# Simon-2023.net
KiCad netlist of a schematic drawn in EAGLE
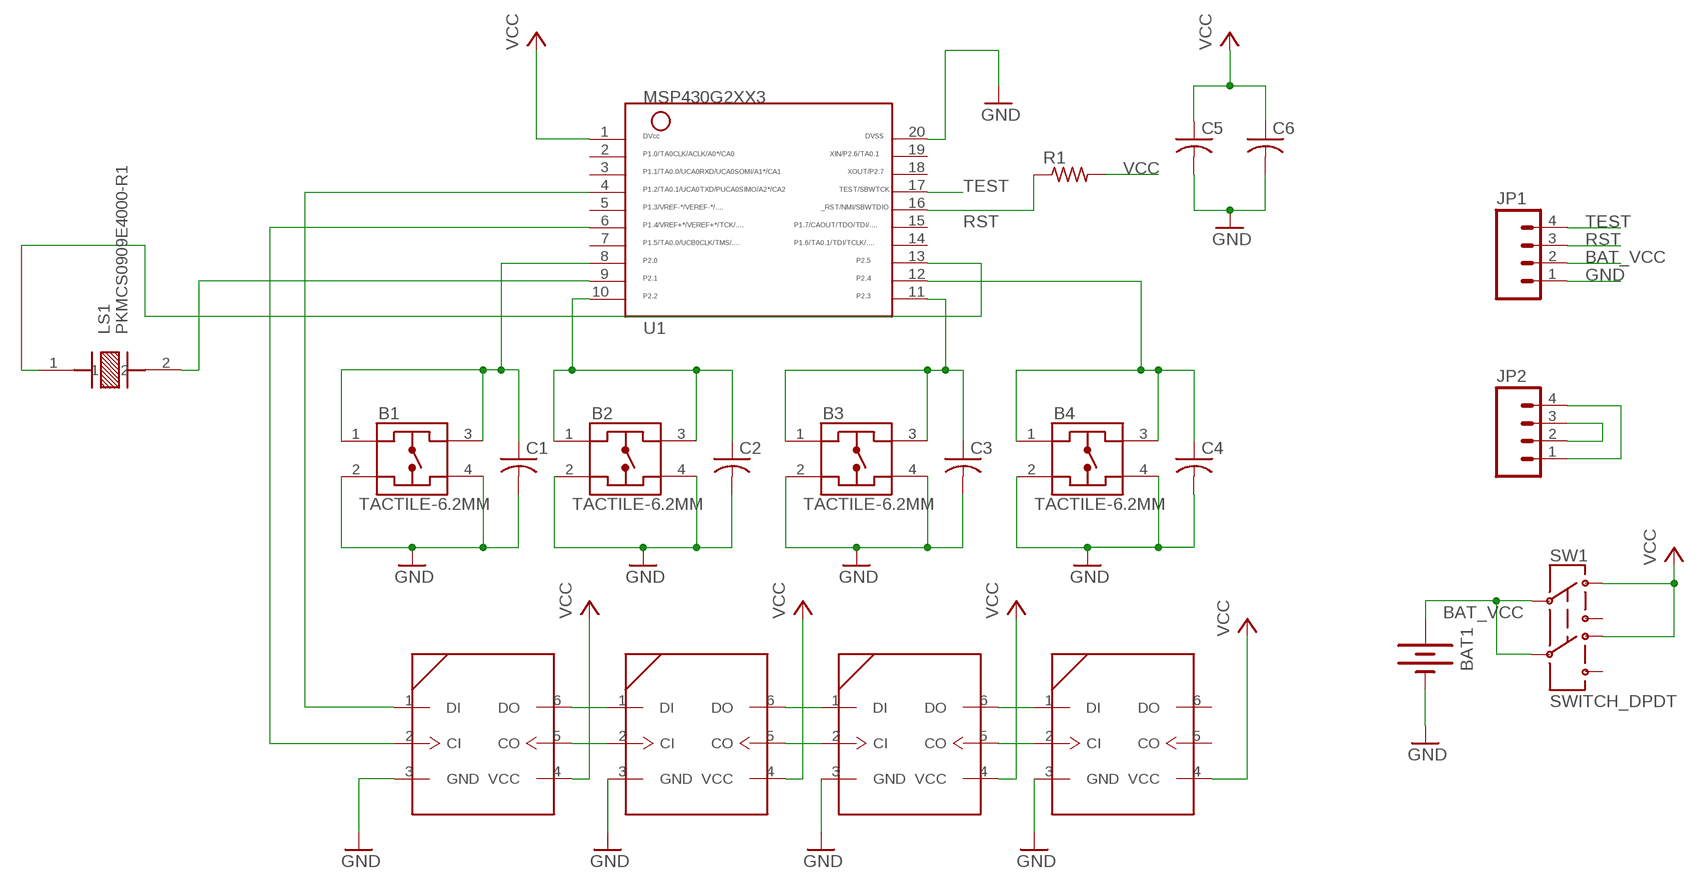
[diagram p0: schematic, sheet 1]

(export (version "E")
  (design (tool "Eeschema 10.0.6"))
  (components
    (comp (ref "B1")
      (value "TACTILE-6.2MM")
      (footprint "eagle-import:222_AM")
      (libsource (lib "eagle-import") (part "TACTILE-6.2MM"))
    )
    (comp (ref "B2")
      (value "TACTILE-6.2MM")
      (footprint "eagle-import:222_AM")
      (libsource (lib "eagle-import") (part "TACTILE-6.2MM"))
    )
    (comp (ref "B3")
      (value "TACTILE-6.2MM")
      (footprint "eagle-import:222_AM")
      (libsource (lib "eagle-import") (part "TACTILE-6.2MM"))
    )
    (comp (ref "B4")
      (value "TACTILE-6.2MM")
      (footprint "eagle-import:222_AM")
      (libsource (lib "eagle-import") (part "TACTILE-6.2MM"))
    )
    (comp (ref "BAT1")
      (value "BATTERY")
      (footprint "eagle-import:BATTERY_PACK_2AA")
      (libsource (lib "eagle-import") (part "BATTERY"))
    )
    (comp (ref "C1")
      (value "C-USC0603")
      (footprint "eagle-import:C0603")
      (libsource (lib "eagle-import") (part "C-USC0603"))
    )
    (comp (ref "C2")
      (value "C-USC0603")
      (footprint "eagle-import:C0603")
      (libsource (lib "eagle-import") (part "C-USC0603"))
    )
    (comp (ref "C3")
      (value "C-USC0603")
      (footprint "eagle-import:C0603")
      (libsource (lib "eagle-import") (part "C-USC0603"))
    )
    (comp (ref "C4")
      (value "C-USC0603")
      (footprint "eagle-import:C0603")
      (libsource (lib "eagle-import") (part "C-USC0603"))
    )
    (comp (ref "C5")
      (value "C-USC1206")
      (footprint "eagle-import:C1206")
      (libsource (lib "eagle-import") (part "C-USC1206"))
    )
    (comp (ref "C6")
      (value "C-USC0603")
      (footprint "eagle-import:C0603")
      (libsource (lib "eagle-import") (part "C-USC0603"))
    )
    (comp (ref "JP1")
      (value "M04LOCK")
      (footprint "eagle-import:1X04_LOCK")
      (libsource (lib "eagle-import") (part "M04LOCK"))
    )
    (comp (ref "JP2")
      (value "M04LOCK")
      (footprint "eagle-import:1X04_LOCK")
      (libsource (lib "eagle-import") (part "M04LOCK"))
    )
    (comp (ref "LED1")
      (value "APA102")
      (footprint "eagle-import:5050")
      (libsource (lib "eagle-import") (part "APA102"))
    )
    (comp (ref "LED2")
      (value "APA102")
      (footprint "eagle-import:5050")
      (libsource (lib "eagle-import") (part "APA102"))
    )
    (comp (ref "LED3")
      (value "APA102")
      (footprint "eagle-import:5050")
      (libsource (lib "eagle-import") (part "APA102"))
    )
    (comp (ref "LED4")
      (value "APA102")
      (footprint "eagle-import:5050")
      (libsource (lib "eagle-import") (part "APA102"))
    )
    (comp (ref "LS1")
      (value "PKMCS0909E4000-R1")
      (footprint "eagle-import:XDCR_PKMCS0909E4000-R1")
      (fields (field (name "DIGI-KEY_PART_NUMBER") "490-9647-1-ND") (field (name "MF") "Murata"))
      (libsource (lib "eagle-import") (part "PKMCS0909E4000-R1"))
    )
    (comp (ref "R1")
      (value "R-US_R1206")
      (footprint "eagle-import:R1206")
      (libsource (lib "eagle-import") (part "R-US_R1206"))
    )
    (comp (ref "SW1")
      (value "SWITCH_DPDT")
      (footprint "eagle-import:JS_DPDT_TH")
      (libsource (lib "eagle-import") (part "SWITCH_DPDT"))
    )
    (comp (ref "U1")
      (value "MSP430G2XX3TSSOP")
      (footprint "eagle-import:PW20")
      (libsource (lib "eagle-import") (part "MSP430G2XX3TSSOP"))
    )
  )
  (nets
    (net (code "1") (name "/BAT_VCC") (class "Default")
      (node (ref "BAT1") (pin "3V") (pinfunction "+_3V") (pintype "power_in"))
      (node (ref "JP1") (pin "2") (pinfunction "2_2") (pintype "passive"))
      (node (ref "SW1") (pin "2") (pinfunction "2_2") (pintype "bidirectional"))
      (node (ref "SW1") (pin "5") (pinfunction "5_5") (pintype "bidirectional"))
    )
    (net (code "2") (name "/RST") (class "Default")
      (node (ref "JP1") (pin "3") (pinfunction "3_3") (pintype "passive"))
      (node (ref "R1") (pin "1") (pinfunction "1_1") (pintype "passive"))
      (node (ref "U1") (pin "16") (pinfunction "16_16") (pintype "bidirectional"))
    )
    (net (code "3") (name "/TEST") (class "Default")
      (node (ref "JP1") (pin "4") (pinfunction "4_4") (pintype "passive"))
      (node (ref "U1") (pin "17") (pinfunction "17_17") (pintype "bidirectional"))
    )
    (net (code "4") (name "GND") (class "Default")
      (node (ref "B1") (pin "2") (pinfunction "2_2") (pintype "passive"))
      (node (ref "B1") (pin "4") (pinfunction "4_4") (pintype "passive"))
      (node (ref "B2") (pin "2") (pinfunction "2_2") (pintype "passive"))
      (node (ref "B2") (pin "4") (pinfunction "4_4") (pintype "passive"))
      (node (ref "B3") (pin "2") (pinfunction "2_2") (pintype "passive"))
      (node (ref "B3") (pin "4") (pinfunction "4_4") (pintype "passive"))
      (node (ref "B4") (pin "2") (pinfunction "2_2") (pintype "passive"))
      (node (ref "B4") (pin "4") (pinfunction "4_4") (pintype "passive"))
      (node (ref "BAT1") (pin "GND") (pinfunction "-_GND") (pintype "power_in"))
      (node (ref "C1") (pin "2") (pinfunction "2_2") (pintype "passive"))
      (node (ref "C2") (pin "2") (pinfunction "2_2") (pintype "passive"))
      (node (ref "C3") (pin "2") (pinfunction "2_2") (pintype "passive"))
      (node (ref "C4") (pin "2") (pinfunction "2_2") (pintype "passive"))
      (node (ref "C5") (pin "2") (pinfunction "2_2") (pintype "passive"))
      (node (ref "C6") (pin "2") (pinfunction "2_2") (pintype "passive"))
      (node (ref "JP1") (pin "1") (pinfunction "1_1") (pintype "passive"))
      (node (ref "LED1") (pin "3") (pinfunction "GND_3") (pintype "power_in"))
      (node (ref "LED2") (pin "3") (pinfunction "GND_3") (pintype "power_in"))
      (node (ref "LED3") (pin "3") (pinfunction "GND_3") (pintype "power_in"))
      (node (ref "LED4") (pin "3") (pinfunction "GND_3") (pintype "power_in"))
      (node (ref "U1") (pin "20") (pinfunction "20_20") (pintype "bidirectional"))
    )
    (net (code "5") (name "Net-(B1-Pad1)") (class "Default")
      (node (ref "B1") (pin "1") (pinfunction "1_1") (pintype "passive"))
      (node (ref "B1") (pin "3") (pinfunction "3_3") (pintype "passive"))
      (node (ref "C1") (pin "1") (pinfunction "1_1") (pintype "passive"))
      (node (ref "U1") (pin "8") (pinfunction "8_8") (pintype "bidirectional"))
    )
    (net (code "6") (name "Net-(B2-Pad1)") (class "Default")
      (node (ref "B2") (pin "1") (pinfunction "1_1") (pintype "passive"))
      (node (ref "B2") (pin "3") (pinfunction "3_3") (pintype "passive"))
      (node (ref "C2") (pin "1") (pinfunction "1_1") (pintype "passive"))
      (node (ref "U1") (pin "10") (pinfunction "10_10") (pintype "bidirectional"))
    )
    (net (code "7") (name "Net-(B3-Pad1)") (class "Default")
      (node (ref "B3") (pin "1") (pinfunction "1_1") (pintype "passive"))
      (node (ref "B3") (pin "3") (pinfunction "3_3") (pintype "passive"))
      (node (ref "C3") (pin "1") (pinfunction "1_1") (pintype "passive"))
      (node (ref "U1") (pin "11") (pinfunction "11_11") (pintype "bidirectional"))
    )
    (net (code "8") (name "Net-(B4-Pad1)") (class "Default")
      (node (ref "B4") (pin "1") (pinfunction "1_1") (pintype "passive"))
      (node (ref "B4") (pin "3") (pinfunction "3_3") (pintype "passive"))
      (node (ref "C4") (pin "1") (pinfunction "1_1") (pintype "passive"))
      (node (ref "U1") (pin "12") (pinfunction "12_12") (pintype "bidirectional"))
    )
    (net (code "9") (name "Net-(JP2-Pad1)") (class "Default")
      (node (ref "JP2") (pin "1") (pinfunction "1_1") (pintype "passive"))
      (node (ref "JP2") (pin "4") (pinfunction "4_4") (pintype "passive"))
    )
    (net (code "10") (name "Net-(JP2-Pad2)") (class "Default")
      (node (ref "JP2") (pin "2") (pinfunction "2_2") (pintype "passive"))
      (node (ref "JP2") (pin "3") (pinfunction "3_3") (pintype "passive"))
    )
    (net (code "11") (name "Net-(LED1-CI)") (class "Default")
      (node (ref "LED1") (pin "2") (pinfunction "CI_2") (pintype "input"))
      (node (ref "U1") (pin "6") (pinfunction "6_6") (pintype "bidirectional"))
    )
    (net (code "12") (name "Net-(LED1-CO)") (class "Default")
      (node (ref "LED1") (pin "5") (pinfunction "CO_5") (pintype "output"))
      (node (ref "LED2") (pin "2") (pinfunction "CI_2") (pintype "input"))
    )
    (net (code "13") (name "Net-(LED1-DI)") (class "Default")
      (node (ref "LED1") (pin "1") (pinfunction "DI_1") (pintype "input"))
      (node (ref "U1") (pin "4") (pinfunction "4_4") (pintype "bidirectional"))
    )
    (net (code "14") (name "Net-(LED1-DO)") (class "Default")
      (node (ref "LED1") (pin "6") (pinfunction "DO_6") (pintype "output"))
      (node (ref "LED2") (pin "1") (pinfunction "DI_1") (pintype "input"))
    )
    (net (code "15") (name "Net-(LED2-CO)") (class "Default")
      (node (ref "LED2") (pin "5") (pinfunction "CO_5") (pintype "output"))
      (node (ref "LED3") (pin "2") (pinfunction "CI_2") (pintype "input"))
    )
    (net (code "16") (name "Net-(LED2-DO)") (class "Default")
      (node (ref "LED2") (pin "6") (pinfunction "DO_6") (pintype "output"))
      (node (ref "LED3") (pin "1") (pinfunction "DI_1") (pintype "input"))
    )
    (net (code "17") (name "Net-(LED3-CO)") (class "Default")
      (node (ref "LED3") (pin "5") (pinfunction "CO_5") (pintype "output"))
      (node (ref "LED4") (pin "2") (pinfunction "CI_2") (pintype "input"))
    )
    (net (code "18") (name "Net-(LED3-DO)") (class "Default")
      (node (ref "LED3") (pin "6") (pinfunction "DO_6") (pintype "output"))
      (node (ref "LED4") (pin "1") (pinfunction "DI_1") (pintype "input"))
    )
    (net (code "19") (name "Net-(LS1-Pad1)") (class "Default")
      (node (ref "LS1") (pin "1") (pinfunction "1_1") (pintype "passive"))
      (node (ref "U1") (pin "13") (pinfunction "13_13") (pintype "bidirectional"))
    )
    (net (code "20") (name "Net-(LS1-Pad2)") (class "Default")
      (node (ref "LS1") (pin "2") (pinfunction "2_2") (pintype "passive"))
      (node (ref "U1") (pin "9") (pinfunction "9_9") (pintype "bidirectional"))
    )
    (net (code "21") (name "VCC") (class "Default")
      (node (ref "C5") (pin "1") (pinfunction "1_1") (pintype "passive"))
      (node (ref "C6") (pin "1") (pinfunction "1_1") (pintype "passive"))
      (node (ref "LED1") (pin "4") (pinfunction "VCC_4") (pintype "power_in"))
      (node (ref "LED2") (pin "4") (pinfunction "VCC_4") (pintype "power_in"))
      (node (ref "LED3") (pin "4") (pinfunction "VCC_4") (pintype "power_in"))
      (node (ref "LED4") (pin "4") (pinfunction "VCC_4") (pintype "power_in"))
      (node (ref "R1") (pin "2") (pinfunction "2_2") (pintype "passive"))
      (node (ref "SW1") (pin "1") (pinfunction "1_1") (pintype "bidirectional"))
      (node (ref "SW1") (pin "4") (pinfunction "4_4") (pintype "bidirectional"))
      (node (ref "U1") (pin "1") (pinfunction "1_1") (pintype "bidirectional"))
    )
    (net (code "22") (name "unconnected-(LED4-CO-Pad5)") (class "Default")
      (node (ref "LED4") (pin "5") (pinfunction "CO_5") (pintype "output"))
    )
    (net (code "23") (name "unconnected-(LED4-DO-Pad6)") (class "Default")
      (node (ref "LED4") (pin "6") (pinfunction "DO_6") (pintype "output"))
    )
    (net (code "24") (name "unconnected-(SW1-Pad3)") (class "Default")
      (node (ref "SW1") (pin "3") (pinfunction "3_3") (pintype "bidirectional"))
    )
    (net (code "25") (name "unconnected-(SW1-Pad6)") (class "Default")
      (node (ref "SW1") (pin "6") (pinfunction "6_6") (pintype "bidirectional"))
    )
    (net (code "26") (name "unconnected-(U1-Pad2)") (class "Default")
      (node (ref "U1") (pin "2") (pinfunction "2_2") (pintype "bidirectional"))
    )
    (net (code "27") (name "unconnected-(U1-Pad3)") (class "Default")
      (node (ref "U1") (pin "3") (pinfunction "3_3") (pintype "bidirectional"))
    )
    (net (code "28") (name "unconnected-(U1-Pad5)") (class "Default")
      (node (ref "U1") (pin "5") (pinfunction "5_5") (pintype "bidirectional"))
    )
    (net (code "29") (name "unconnected-(U1-Pad7)") (class "Default")
      (node (ref "U1") (pin "7") (pinfunction "7_7") (pintype "bidirectional"))
    )
    (net (code "30") (name "unconnected-(U1-Pad14)") (class "Default")
      (node (ref "U1") (pin "14") (pinfunction "14_14") (pintype "bidirectional"))
    )
    (net (code "31") (name "unconnected-(U1-Pad15)") (class "Default")
      (node (ref "U1") (pin "15") (pinfunction "15_15") (pintype "bidirectional"))
    )
    (net (code "32") (name "unconnected-(U1-Pad18)") (class "Default")
      (node (ref "U1") (pin "18") (pinfunction "18_18") (pintype "bidirectional"))
    )
    (net (code "33") (name "unconnected-(U1-Pad19)") (class "Default")
      (node (ref "U1") (pin "19") (pinfunction "19_19") (pintype "bidirectional"))
    )
  )
)
